# RgbControllerWithIR.net
KiCad netlist of a schematic drawn in EAGLE
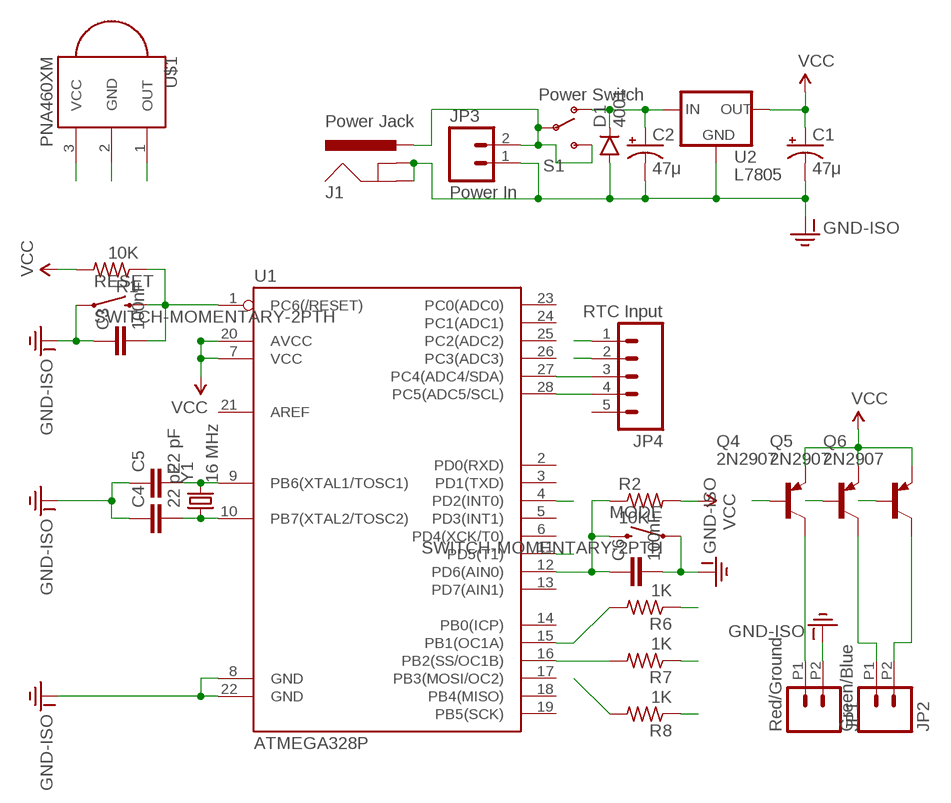
[diagram p0: schematic, sheet 1]

(export (version "E")
  (design (tool "Eeschema 10.0.6"))
  (components
    (comp (ref "C1")
      (value "47μ")
      (footprint "eagle-import:ELECTROLYTIC_CAP")
      (libsource (lib "eagle-import") (part "ELECTROLYTIC_CAP2.54MM"))
    )
    (comp (ref "C2")
      (value "47μ")
      (footprint "eagle-import:ELECTROLYTIC_CAP")
      (libsource (lib "eagle-import") (part "ELECTROLYTIC_CAP2.54MM"))
    )
    (comp (ref "C3")
      (value "100nF")
      (footprint "eagle-import:CAP-PTH-SMALL")
      (libsource (lib "eagle-import") (part "CAPPTH"))
    )
    (comp (ref "C4")
      (value "22 pF")
      (footprint "eagle-import:CAP-PTH-SMALL")
      (libsource (lib "eagle-import") (part "CAPPTH"))
    )
    (comp (ref "C5")
      (value "22 pF")
      (footprint "eagle-import:CAP-PTH-SMALL")
      (libsource (lib "eagle-import") (part "CAPPTH"))
    )
    (comp (ref "C6")
      (value "100nF")
      (footprint "eagle-import:CAP-PTH-SMALL")
      (libsource (lib "eagle-import") (part "CAPPTH"))
    )
    (comp (ref "D1")
      (value "4001")
      (footprint "eagle-import:DIODE-1N4001")
      (libsource (lib "eagle-import") (part "DIODEPTH"))
    )
    (comp (ref "J1")
      (value "Power Jack")
      (footprint "eagle-import:POWER_JACK")
      (libsource (lib "eagle-import") (part "POWER_JACK{dblquote}"))
    )
    (comp (ref "JP1")
      (value "Red/Ground")
      (footprint "eagle-import:1X02_2.54_SCREWTERM")
      (libsource (lib "eagle-import") (part "M022.54MM_SCREWTERM"))
    )
    (comp (ref "JP2")
      (value "Green/Blue")
      (footprint "eagle-import:1X02_2.54_SCREWTERM")
      (libsource (lib "eagle-import") (part "M022.54MM_SCREWTERM"))
    )
    (comp (ref "JP3")
      (value "Power In")
      (footprint "eagle-import:SCREWTERMINAL-5MM-2")
      (libsource (lib "eagle-import") (part "M025MM"))
    )
    (comp (ref "JP4")
      (value "RTC Input")
      (footprint "eagle-import:1X05_LONGPADS")
      (libsource (lib "eagle-import") (part "M05PTH_LONGPADS"))
    )
    (comp (ref "MODE")
      (value "SWITCH-MOMENTARY-2PTH")
      (footprint "eagle-import:TACTILE-PTH")
      (libsource (lib "eagle-import") (part "SWITCH-MOMENTARY-2PTH"))
    )
    (comp (ref "Q4")
      (value "2N2907")
      (footprint "eagle-import:TO92-EBC-OVAL")
      (libsource (lib "eagle-import") (part "2N2907"))
    )
    (comp (ref "Q5")
      (value "2N2907")
      (footprint "eagle-import:TO92-EBC-OVAL")
      (libsource (lib "eagle-import") (part "2N2907"))
    )
    (comp (ref "Q6")
      (value "2N2907")
      (footprint "eagle-import:TO92-EBC-OVAL")
      (libsource (lib "eagle-import") (part "2N2907"))
    )
    (comp (ref "R1")
      (value "10K")
      (footprint "eagle-import:0207_9")
      (libsource (lib "eagle-import") (part "R-US_0207/9"))
    )
    (comp (ref "R2")
      (value "10K")
      (footprint "eagle-import:0207_9")
      (libsource (lib "eagle-import") (part "R-US_0207/9"))
    )
    (comp (ref "R6")
      (value "1K")
      (footprint "eagle-import:0207_9")
      (libsource (lib "eagle-import") (part "R-US_0207/9"))
    )
    (comp (ref "R7")
      (value "1K")
      (footprint "eagle-import:0207_9")
      (libsource (lib "eagle-import") (part "R-US_0207/9"))
    )
    (comp (ref "R8")
      (value "1K")
      (footprint "eagle-import:0207_9")
      (libsource (lib "eagle-import") (part "R-US_0207/9"))
    )
    (comp (ref "RESET")
      (value "SWITCH-MOMENTARY-2PTH")
      (footprint "eagle-import:TACTILE-PTH")
      (libsource (lib "eagle-import") (part "SWITCH-MOMENTARY-2PTH"))
    )
    (comp (ref "S1")
      (value "Power Switch")
      (footprint "eagle-import:SWITCH-SPDT")
      (libsource (lib "eagle-import") (part "SWITCH-SPDTPTH"))
    )
    (comp (ref "U$1")
      (value "PNA460XM")
      (footprint "eagle-import:PNA460XM")
      (libsource (lib "eagle-import") (part "PNA460XM"))
    )
    (comp (ref "U1")
      (value "ATMEGA328P")
      (footprint "eagle-import:DIL28-3")
      (libsource (lib "eagle-import") (part "ATMEGA328P_PDIP"))
    )
    (comp (ref "U2")
      (value "L7805")
      (footprint "eagle-import:78XXL")
      (libsource (lib "eagle-import") (part "V_REG_78XXSIDE"))
    )
    (comp (ref "Y1")
      (value "16 MHz")
      (footprint "eagle-import:HC49US")
      (libsource (lib "eagle-import") (part "CRYSTALHC49US"))
    )
  )
  (nets
    (net (code "1") (name "/BLUE") (class "Default")
      (node (ref "Q6") (pin "B") (pinfunction "B_B") (pintype "passive"))
      (node (ref "R8") (pin "1") (pinfunction "1_1") (pintype "passive"))
    )
    (net (code "2") (name "/GREEN") (class "Default")
      (node (ref "Q5") (pin "B") (pinfunction "B_B") (pintype "passive"))
      (node (ref "R7") (pin "1") (pinfunction "1_1") (pintype "passive"))
    )
    (net (code "3") (name "/PD2") (class "Default")
      (node (ref "U$1") (pin "1") (pinfunction "OUT_1") (pintype "output"))
      (node (ref "U1") (pin "4") (pinfunction "PD2(INT0)_4") (pintype "bidirectional"))
    )
    (net (code "4") (name "/PD5") (class "Default")
      (node (ref "R8") (pin "2") (pinfunction "2_2") (pintype "passive"))
      (node (ref "U1") (pin "11") (pinfunction "PD5(T1)_11") (pintype "bidirectional"))
    )
    (net (code "5") (name "/RED") (class "Default")
      (node (ref "Q4") (pin "B") (pinfunction "B_B") (pintype "passive"))
      (node (ref "R6") (pin "1") (pinfunction "1_1") (pintype "passive"))
    )
    (net (code "6") (name "GND-ISO") (class "Default")
      (node (ref "C1") (pin "-") (pinfunction "-_-") (pintype "passive"))
      (node (ref "C2") (pin "-") (pinfunction "-_-") (pintype "passive"))
      (node (ref "C3") (pin "1") (pinfunction "1_1") (pintype "passive"))
      (node (ref "C4") (pin "1") (pinfunction "1_1") (pintype "passive"))
      (node (ref "C5") (pin "1") (pinfunction "1_1") (pintype "passive"))
      (node (ref "C6") (pin "2") (pinfunction "2_2") (pintype "passive"))
      (node (ref "D1") (pin "A") (pinfunction "A_A") (pintype "passive"))
      (node (ref "J1") (pin "GND") (pinfunction "GND_GND") (pintype "bidirectional"))
      (node (ref "J1") (pin "GNDBREAK") (pinfunction "GNDBREAK_GNDBREAK") (pintype "bidirectional"))
      (node (ref "JP1") (pin "P2") (pinfunction "2_P2") (pintype "passive"))
      (node (ref "JP3") (pin "1") (pinfunction "1_1") (pintype "passive"))
      (node (ref "JP4") (pin "1") (pinfunction "1_1") (pintype "passive"))
      (node (ref "MODE") (pin "1") (pinfunction "1_1") (pintype "passive"))
      (node (ref "RESET") (pin "1") (pinfunction "1_1") (pintype "passive"))
      (node (ref "U$1") (pin "2") (pinfunction "GND_2") (pintype "power_in"))
      (node (ref "U1") (pin "22") (pinfunction "GND_22") (pintype "bidirectional"))
      (node (ref "U1") (pin "8") (pinfunction "GND_8") (pintype "bidirectional"))
      (node (ref "U2") (pin "GND") (pinfunction "GND_GND") (pintype "input"))
    )
    (net (code "7") (name "Net-(JP1-1)") (class "Default")
      (node (ref "JP1") (pin "P1") (pinfunction "1_P1") (pintype "passive"))
      (node (ref "Q4") (pin "C") (pinfunction "C_C") (pintype "passive"))
    )
    (net (code "8") (name "Net-(JP2-1)") (class "Default")
      (node (ref "JP2") (pin "P1") (pinfunction "1_P1") (pintype "passive"))
      (node (ref "Q5") (pin "C") (pinfunction "C_C") (pintype "passive"))
    )
    (net (code "9") (name "Net-(JP2-2)") (class "Default")
      (node (ref "JP2") (pin "P2") (pinfunction "2_P2") (pintype "passive"))
      (node (ref "Q6") (pin "C") (pinfunction "C_C") (pintype "passive"))
    )
    (net (code "10") (name "Net-(MODE-2)") (class "Default")
      (node (ref "C6") (pin "1") (pinfunction "1_1") (pintype "passive"))
      (node (ref "MODE") (pin "3") (pinfunction "2_3") (pintype "passive"))
      (node (ref "R2") (pin "1") (pinfunction "1_1") (pintype "passive"))
      (node (ref "U1") (pin "12") (pinfunction "PD6(AIN0)_12") (pintype "bidirectional"))
    )
    (net (code "11") (name "Net-(RESET-2)") (class "Default")
      (node (ref "C3") (pin "2") (pinfunction "2_2") (pintype "passive"))
      (node (ref "R1") (pin "1") (pinfunction "1_1") (pintype "passive"))
      (node (ref "RESET") (pin "3") (pinfunction "2_3") (pintype "passive"))
      (node (ref "U1") (pin "1") (pinfunction "PC6(/RESET)_1") (pintype "bidirectional"))
    )
    (net (code "12") (name "Net-(S1-O)") (class "Default")
      (node (ref "C2") (pin "+") (pinfunction "+_+") (pintype "passive"))
      (node (ref "D1") (pin "C") (pinfunction "C_C") (pintype "passive"))
      (node (ref "S1") (pin "1") (pinfunction "O_1") (pintype "passive"))
      (node (ref "U2") (pin "IN") (pinfunction "IN_IN") (pintype "input"))
    )
    (net (code "13") (name "Net-(S1-P)") (class "Default")
      (node (ref "J1") (pin "PWR") (pinfunction "PWR_PWR") (pintype "bidirectional"))
      (node (ref "JP3") (pin "2") (pinfunction "2_2") (pintype "passive"))
      (node (ref "S1") (pin "2") (pinfunction "P_2") (pintype "passive"))
      (node (ref "S1") (pin "3") (pinfunction "S_3") (pintype "passive"))
    )
    (net (code "14") (name "Net-(U1-PB1(OC1A))") (class "Default")
      (node (ref "R6") (pin "2") (pinfunction "2_2") (pintype "passive"))
      (node (ref "U1") (pin "15") (pinfunction "PB1(OC1A)_15") (pintype "bidirectional"))
    )
    (net (code "15") (name "Net-(U1-PB2(SS{slash}OC1B))") (class "Default")
      (node (ref "R7") (pin "2") (pinfunction "2_2") (pintype "passive"))
      (node (ref "U1") (pin "16") (pinfunction "PB2(SS/OC1B)_16") (pintype "bidirectional"))
    )
    (net (code "16") (name "Net-(U1-PB6(XTAL1{slash}TOSC1))") (class "Default")
      (node (ref "C5") (pin "2") (pinfunction "2_2") (pintype "passive"))
      (node (ref "U1") (pin "9") (pinfunction "PB6(XTAL1/TOSC1)_9") (pintype "bidirectional"))
      (node (ref "Y1") (pin "2") (pinfunction "2_2") (pintype "passive"))
    )
    (net (code "17") (name "Net-(U1-PB7(XTAL2{slash}TOSC2))") (class "Default")
      (node (ref "C4") (pin "2") (pinfunction "2_2") (pintype "passive"))
      (node (ref "U1") (pin "10") (pinfunction "PB7(XTAL2/TOSC2)_10") (pintype "bidirectional"))
      (node (ref "Y1") (pin "1") (pinfunction "1_1") (pintype "passive"))
    )
    (net (code "18") (name "Net-(U1-PC4(ADC4{slash}SDA))") (class "Default")
      (node (ref "JP4") (pin "3") (pinfunction "3_3") (pintype "passive"))
      (node (ref "U1") (pin "27") (pinfunction "PC4(ADC4/SDA)_27") (pintype "bidirectional"))
    )
    (net (code "19") (name "Net-(U1-PC5(ADC5{slash}SCL))") (class "Default")
      (node (ref "JP4") (pin "4") (pinfunction "4_4") (pintype "passive"))
      (node (ref "U1") (pin "28") (pinfunction "PC5(ADC5/SCL)_28") (pintype "bidirectional"))
    )
    (net (code "20") (name "VCC") (class "Default")
      (node (ref "C1") (pin "+") (pinfunction "+_+") (pintype "passive"))
      (node (ref "JP4") (pin "2") (pinfunction "2_2") (pintype "passive"))
      (node (ref "Q4") (pin "E") (pinfunction "E_E") (pintype "passive"))
      (node (ref "Q5") (pin "E") (pinfunction "E_E") (pintype "passive"))
      (node (ref "Q6") (pin "E") (pinfunction "E_E") (pintype "passive"))
      (node (ref "R1") (pin "2") (pinfunction "2_2") (pintype "passive"))
      (node (ref "R2") (pin "2") (pinfunction "2_2") (pintype "passive"))
      (node (ref "U$1") (pin "3") (pinfunction "VCC_3") (pintype "power_in"))
      (node (ref "U1") (pin "20") (pinfunction "AVCC_20") (pintype "bidirectional"))
      (node (ref "U1") (pin "7") (pinfunction "VCC_7") (pintype "bidirectional"))
      (node (ref "U2") (pin "OUT") (pinfunction "OUT_OUT") (pintype "passive"))
    )
    (net (code "21") (name "unconnected-(JP4-Pad5)") (class "Default")
      (node (ref "JP4") (pin "5") (pinfunction "5_5") (pintype "passive"))
    )
    (net (code "22") (name "unconnected-(U1-AREF-Pad21)") (class "Default")
      (node (ref "U1") (pin "21") (pinfunction "AREF_21") (pintype "bidirectional"))
    )
    (net (code "23") (name "unconnected-(U1-PB0(ICP)-Pad14)") (class "Default")
      (node (ref "U1") (pin "14") (pinfunction "PB0(ICP)_14") (pintype "bidirectional"))
    )
    (net (code "24") (name "unconnected-(U1-PB3(MOSI{slash}OC2)-Pad17)") (class "Default")
      (node (ref "U1") (pin "17") (pinfunction "PB3(MOSI/OC2)_17") (pintype "bidirectional"))
    )
    (net (code "25") (name "unconnected-(U1-PB4(MISO)-Pad18)") (class "Default")
      (node (ref "U1") (pin "18") (pinfunction "PB4(MISO)_18") (pintype "bidirectional"))
    )
    (net (code "26") (name "unconnected-(U1-PB5(SCK)-Pad19)") (class "Default")
      (node (ref "U1") (pin "19") (pinfunction "PB5(SCK)_19") (pintype "bidirectional"))
    )
    (net (code "27") (name "unconnected-(U1-PC0(ADC0)-Pad23)") (class "Default")
      (node (ref "U1") (pin "23") (pinfunction "PC0(ADC0)_23") (pintype "bidirectional"))
    )
    (net (code "28") (name "unconnected-(U1-PC1(ADC1)-Pad24)") (class "Default")
      (node (ref "U1") (pin "24") (pinfunction "PC1(ADC1)_24") (pintype "bidirectional"))
    )
    (net (code "29") (name "unconnected-(U1-PC2(ADC2)-Pad25)") (class "Default")
      (node (ref "U1") (pin "25") (pinfunction "PC2(ADC2)_25") (pintype "bidirectional"))
    )
    (net (code "30") (name "unconnected-(U1-PC3(ADC3)-Pad26)") (class "Default")
      (node (ref "U1") (pin "26") (pinfunction "PC3(ADC3)_26") (pintype "bidirectional"))
    )
    (net (code "31") (name "unconnected-(U1-PD0(RXD)-Pad2)") (class "Default")
      (node (ref "U1") (pin "2") (pinfunction "PD0(RXD)_2") (pintype "bidirectional"))
    )
    (net (code "32") (name "unconnected-(U1-PD1(TXD)-Pad3)") (class "Default")
      (node (ref "U1") (pin "3") (pinfunction "PD1(TXD)_3") (pintype "bidirectional"))
    )
    (net (code "33") (name "unconnected-(U1-PD3(INT1)-Pad5)") (class "Default")
      (node (ref "U1") (pin "5") (pinfunction "PD3(INT1)_5") (pintype "bidirectional"))
    )
    (net (code "34") (name "unconnected-(U1-PD4(XCK{slash}T0)-Pad6)") (class "Default")
      (node (ref "U1") (pin "6") (pinfunction "PD4(XCK/T0)_6") (pintype "bidirectional"))
    )
    (net (code "35") (name "unconnected-(U1-PD7(AIN1)-Pad13)") (class "Default")
      (node (ref "U1") (pin "13") (pinfunction "PD7(AIN1)_13") (pintype "bidirectional"))
    )
  )
)
